# USB.net
KiCad netlist of a schematic drawn in Altium Designer
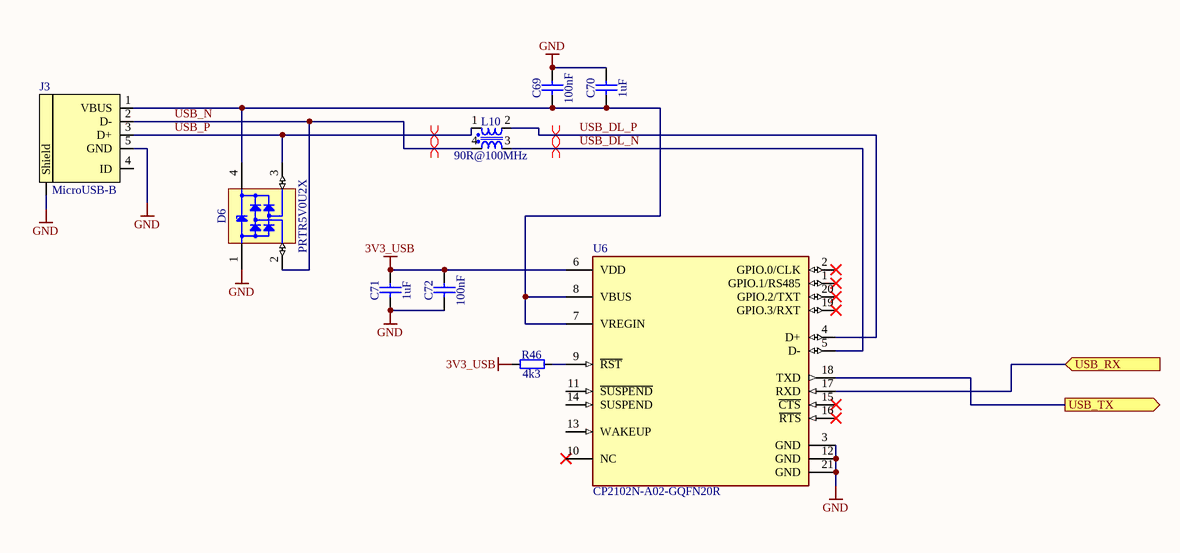
[diagram p0: USB.SchDoc]

(export (version "E")
  (design (tool "Eeschema 10.0.6"))
  (components
    (comp (ref "C69")
      (value "100nF")
      (footprint "CAPC1005X55N")
      (description "Non-polarised capacitor")
      (fields
        (field (name "PART NUMBER") "CC0402_100NF_16V_10%_X5R")
        (field (name "VOLTAGE") "16V")
        (field (name "AUTHOR") "CERN DEM JLC")
      )
      (libsource (lib "Capacitors") (part "Capacitor - non polarized"))
    )
    (comp (ref "C70")
      (value "1uF")
      (footprint "CAPC1005X55N")
      (description "Non-polarised capacitor")
      (fields
        (field (name "PART NUMBER") "CC0402_1UF_16V_10%_X5R")
        (field (name "VOLTAGE") "16V")
        (field (name "AUTHOR") "CERN DEM JLC")
      )
      (libsource (lib "Capacitors") (part "Capacitor - non polarized"))
    )
    (comp (ref "C71")
      (value "1uF")
      (footprint "CAPC1005X55N")
      (description "Non-polarised capacitor")
      (fields
        (field (name "PART NUMBER") "CC0402_1UF_16V_10%_X5R")
        (field (name "VOLTAGE") "16V")
        (field (name "AUTHOR") "CERN DEM JLC")
      )
      (libsource (lib "Capacitors") (part "Capacitor - non polarized"))
    )
    (comp (ref "C72")
      (value "100nF")
      (footprint "CAPC1005X55N")
      (description "Non-polarised capacitor")
      (fields
        (field (name "PART NUMBER") "CC0402_100NF_16V_10%_X5R")
        (field (name "VOLTAGE") "16V")
        (field (name "AUTHOR") "CERN DEM JLC")
      )
      (libsource (lib "Capacitors") (part "Capacitor - non polarized"))
    )
    (comp (ref "D6")
      (value "PRTR5V0U2X")
      (footprint "SOT190P230X110-4N")
      (description "Ultra Low Capacitance Double Rail-to-Rail ESD Protection Diode")
      (fields
        (field (name "VOLTAGE") "5.5V")
        (field (name "MANUFACTURER") "NXP SEMICONDUCTORS")
        (field (name "AUTHOR") "CERN DEM JLC")
      )
      (libsource (lib "ICs And Semiconductors") (part "PRTR5V0U2X"))
    )
    (comp (ref "J3")
      (value "MicroUSB-B")
      (footprint "USB-Micro-B-RA-SMD-PiP")
      (description "MicroUSB-B-SMT")
      (fields
        (field (name "PART NUMBER") "USB-Micro-B-RA-SMD-PiP")
        (field (name "MANUFACTURER") "Allen Creations Corp.")
        (field (name "PUBLISHER") "Nordic Semiconductor")
      )
      (libsource (lib "pca10028") (part "MiniUSB-AB-SMT"))
    )
    (comp (ref "L10")
      (value "90R@100MHz")
      (footprint "IND_MURATA_DLW21S")
      (description "Inductor Common Mode")
      (fields
        (field (name "PART NUMBER") "IND_MURATA_DLW21SN900SQ2L")
        (field (name "POWER") "330mA")
        (field (name "AUTHOR") "CERN DEM JLC")
      )
      (libsource (lib "Inductors & Transformers") (part "Inductor Common Mode 1Dot-2 4Dot-3"))
    )
    (comp (ref "R46")
      (value "4k3")
      (footprint "RESC1005X40N")
      (description "Resistor - 1%")
      (fields
        (field (name "PART NUMBER") "R0402_4K3_1%_0.0625W_100PPM")
        (field (name "POWER") "0.0625W")
        (field (name "AUTHOR") "CERN DEM JLC")
      )
      (libsource (lib "Resistors") (part "Resistor - 1%"))
    )
    (comp (ref "U6")
      (value "CP2102N-A02-GQFN20R")
      (footprint "FP-CP2102N-A02-GQFN20R-MFG")
      (description "IC USB TO UART BRIDGE QFN20")
      (libsource (lib "Altium Content Vault") (part "12297b18919ed2bc2a0fed00377f037"))
    )
  )
  (nets
    (net (code "1") (name "/USB_DL_N") (class "Default")
      (node (ref "L10") (pin "3") (pinfunction "3_3") (pintype "passive"))
      (node (ref "U6") (pin "5") (pinfunction "D-_5") (pintype "bidirectional"))
    )
    (net (code "2") (name "/USB_DL_P") (class "Default")
      (node (ref "L10") (pin "2") (pinfunction "2_2") (pintype "passive"))
      (node (ref "U6") (pin "4") (pinfunction "D+_4") (pintype "bidirectional"))
    )
    (net (code "3") (name "/USB_N") (class "Default")
      (node (ref "D6") (pin "2") (pinfunction "I/O1_2") (pintype "bidirectional"))
      (node (ref "J3") (pin "2") (pinfunction "D-_2") (pintype "passive"))
      (node (ref "L10") (pin "4") (pinfunction "4_4") (pintype "passive"))
    )
    (net (code "4") (name "/USB_P") (class "Default")
      (node (ref "D6") (pin "3") (pinfunction "I/O2_3") (pintype "bidirectional"))
      (node (ref "J3") (pin "3") (pinfunction "D+_3") (pintype "passive"))
      (node (ref "L10") (pin "1") (pinfunction "1_1") (pintype "passive"))
    )
    (net (code "5") (name "/USB_RX") (class "Default")
      (node (ref "U6") (pin "17") (pinfunction "RXD_17") (pintype "input"))
    )
    (net (code "6") (name "/USB_TX") (class "Default")
      (node (ref "U6") (pin "18") (pinfunction "TXD_18") (pintype "output"))
    )
    (net (code "7") (name "3V3_USB") (class "Default")
      (node (ref "C71") (pin "2") (pinfunction "2_2") (pintype "passive"))
      (node (ref "C72") (pin "2") (pinfunction "2_2") (pintype "passive"))
      (node (ref "R46") (pin "1") (pinfunction "1_1") (pintype "passive"))
      (node (ref "U6") (pin "6") (pinfunction "VDD_6") (pintype "power_in"))
    )
    (net (code "8") (name "GND") (class "Default")
      (node (ref "C69") (pin "2") (pinfunction "2_2") (pintype "passive"))
      (node (ref "C70") (pin "2") (pinfunction "2_2") (pintype "passive"))
      (node (ref "C71") (pin "1") (pinfunction "1_1") (pintype "passive"))
      (node (ref "C72") (pin "1") (pinfunction "1_1") (pintype "passive"))
      (node (ref "D6") (pin "1") (pinfunction "GND_1") (pintype "power_in"))
      (node (ref "J3") (pin "5") (pinfunction "GND_5") (pintype "power_in"))
      (node (ref "J3") (pin "6") (pinfunction "Shield_6") (pintype "power_in"))
      (node (ref "U6") (pin "12") (pinfunction "GND_12") (pintype "power_in"))
      (node (ref "U6") (pin "21") (pinfunction "GND_21") (pintype "power_in"))
      (node (ref "U6") (pin "3") (pinfunction "GND_3") (pintype "power_in"))
    )
    (net (code "9") (name "Net-(D6-VCC)") (class "Default")
      (node (ref "C69") (pin "1") (pinfunction "1_1") (pintype "passive"))
      (node (ref "C70") (pin "1") (pinfunction "1_1") (pintype "passive"))
      (node (ref "D6") (pin "4") (pinfunction "VCC_4") (pintype "power_in"))
      (node (ref "J3") (pin "1") (pinfunction "VBUS_1") (pintype "power_in"))
      (node (ref "U6") (pin "7") (pinfunction "VREGIN_7") (pintype "passive"))
      (node (ref "U6") (pin "8") (pinfunction "VBUS_8") (pintype "power_in"))
    )
    (net (code "10") (name "Net-(U6-~{RST})") (class "Default")
      (node (ref "R46") (pin "2") (pinfunction "2_2") (pintype "passive"))
      (node (ref "U6") (pin "9") (pinfunction "~{RST}_9") (pintype "input"))
    )
    (net (code "11") (name "unconnected-(J3-ID-Pad4)") (class "Default")
      (node (ref "J3") (pin "4") (pinfunction "ID_4") (pintype "passive"))
    )
    (net (code "12") (name "unconnected-(U6-GPIO.0{slash}CLK-Pad2)") (class "Default")
      (node (ref "U6") (pin "2") (pinfunction "GPIO.0/CLK_2") (pintype "bidirectional+no_connect"))
    )
    (net (code "13") (name "unconnected-(U6-GPIO.1{slash}RS485-Pad1)") (class "Default")
      (node (ref "U6") (pin "1") (pinfunction "GPIO.1/RS485_1") (pintype "bidirectional+no_connect"))
    )
    (net (code "14") (name "unconnected-(U6-GPIO.2{slash}TXT-Pad20)") (class "Default")
      (node (ref "U6") (pin "20") (pinfunction "GPIO.2/TXT_20") (pintype "bidirectional+no_connect"))
    )
    (net (code "15") (name "unconnected-(U6-GPIO.3{slash}RXT-Pad19)") (class "Default")
      (node (ref "U6") (pin "19") (pinfunction "GPIO.3/RXT_19") (pintype "bidirectional+no_connect"))
    )
    (net (code "16") (name "unconnected-(U6-NC-Pad10)") (class "Default")
      (node (ref "U6") (pin "10") (pinfunction "NC_10") (pintype "passive+no_connect"))
    )
    (net (code "17") (name "unconnected-(U6-SUSPEND-Pad14)") (class "Default")
      (node (ref "U6") (pin "14") (pinfunction "SUSPEND_14") (pintype "input"))
    )
    (net (code "18") (name "unconnected-(U6-WAKEUP-Pad13)") (class "Default")
      (node (ref "U6") (pin "13") (pinfunction "WAKEUP_13") (pintype "input"))
    )
    (net (code "19") (name "unconnected-(U6-~{CTS}-Pad15)") (class "Default")
      (node (ref "U6") (pin "15") (pinfunction "~{CTS}_15") (pintype "input+no_connect"))
    )
    (net (code "20") (name "unconnected-(U6-~{RTS}-Pad16)") (class "Default")
      (node (ref "U6") (pin "16") (pinfunction "~{RTS}_16") (pintype "input+no_connect"))
    )
    (net (code "21") (name "unconnected-(U6-~{SUSPEND}-Pad11)") (class "Default")
      (node (ref "U6") (pin "11") (pinfunction "~{SUSPEND}_11") (pintype "input"))
    )
  )
)
